# SiLabsProg2_V14C.net
KiCad netlist of a schematic drawn in Altium Designer
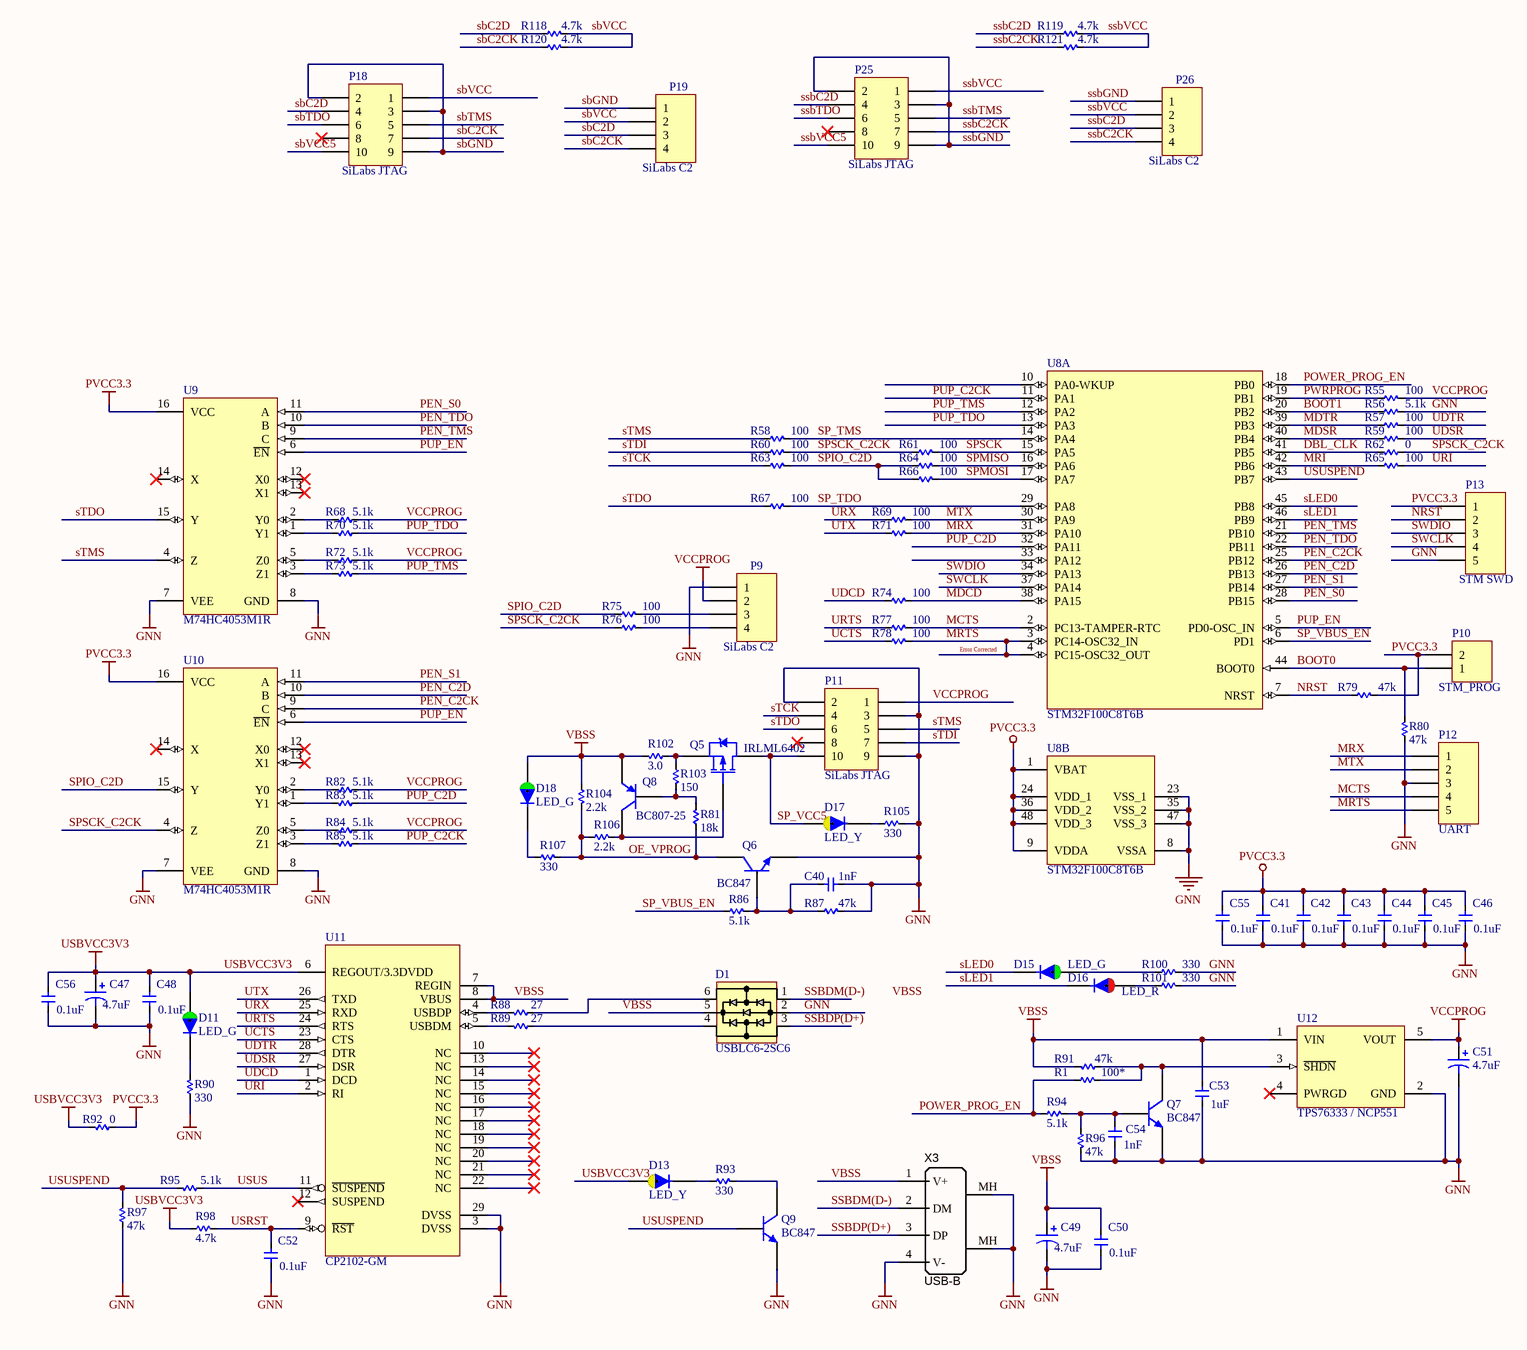
[diagram p0: SiLabsProg2_V14C.SchDoc]

(export (version "E")
  (design (tool "Eeschema 10.0.6"))
  (components
    (comp (ref "C40")
      (value "1nF")
      (footprint "R1608_CAP")
      (description "Capacitor")
      (fields (field (name "MANUFACTURER") "Generic Components") (field (name "PUBLISHER") "Altium Limited"))
      (libsource (lib "Passive_RC") (part "CAP"))
    )
    (comp (ref "C41")
      (value "0.1uF")
      (footprint "R1005_CAP")
      (description "Capacitor")
      (fields (field (name "MANUFACTURER") "Generic Components") (field (name "PUBLISHER") "Altium Limited"))
      (libsource (lib "Passive_RC") (part "CAP"))
    )
    (comp (ref "C42")
      (value "0.1uF")
      (footprint "R1005_CAP")
      (description "Capacitor")
      (fields (field (name "MANUFACTURER") "Generic Components") (field (name "PUBLISHER") "Altium Limited"))
      (libsource (lib "Passive_RC") (part "CAP"))
    )
    (comp (ref "C43")
      (value "0.1uF")
      (footprint "R1005_CAP")
      (description "Capacitor")
      (fields (field (name "MANUFACTURER") "Generic Components") (field (name "PUBLISHER") "Altium Limited"))
      (libsource (lib "Passive_RC") (part "CAP"))
    )
    (comp (ref "C44")
      (value "0.1uF")
      (footprint "R1005_CAP")
      (description "Capacitor")
      (fields (field (name "MANUFACTURER") "Generic Components") (field (name "PUBLISHER") "Altium Limited"))
      (libsource (lib "Passive_RC") (part "CAP"))
    )
    (comp (ref "C45")
      (value "0.1uF")
      (footprint "R1005_CAP")
      (description "Capacitor")
      (fields (field (name "MANUFACTURER") "Generic Components") (field (name "PUBLISHER") "Altium Limited"))
      (libsource (lib "Passive_RC") (part "CAP"))
    )
    (comp (ref "C46")
      (value "0.1uF")
      (footprint "R1005_CAP")
      (description "Capacitor")
      (fields (field (name "MANUFACTURER") "Generic Components") (field (name "PUBLISHER") "Altium Limited"))
      (libsource (lib "Passive_RC") (part "CAP"))
    )
    (comp (ref "C47")
      (value "4.7uF")
      (footprint "CAPC3225L")
      (description "Polarized Capacitor (Radial)")
      (fields (field (name "PUBLISHER") "Altium Limited"))
      (libsource (lib "Miscellaneous Devices") (part "Cap Pol1"))
    )
    (comp (ref "C48")
      (value "0.1uF")
      (footprint "R1005_CAP")
      (description "Capacitor")
      (fields (field (name "MANUFACTURER") "Generic Components") (field (name "PUBLISHER") "Altium Limited"))
      (libsource (lib "Passive_RC") (part "CAP"))
    )
    (comp (ref "C49")
      (value "4.7uF")
      (footprint "CAPC3225L")
      (description "Polarized Capacitor (Radial)")
      (fields (field (name "PUBLISHER") "Altium Limited"))
      (libsource (lib "Miscellaneous Devices") (part "Cap Pol1"))
    )
    (comp (ref "C50")
      (value "0.1uF")
      (footprint "R1005_CAP")
      (description "Capacitor")
      (fields (field (name "MANUFACTURER") "Generic Components") (field (name "PUBLISHER") "Altium Limited"))
      (libsource (lib "Passive_RC") (part "CAP"))
    )
    (comp (ref "C51")
      (value "4.7uF")
      (footprint "CAPC3225L")
      (description "Polarized Capacitor (Radial)")
      (fields (field (name "PUBLISHER") "Altium Limited"))
      (libsource (lib "Miscellaneous Devices") (part "Cap Pol1"))
    )
    (comp (ref "C52")
      (value "0.1uF")
      (footprint "R1005_CAP")
      (description "Capacitor")
      (fields (field (name "MANUFACTURER") "Generic Components") (field (name "PUBLISHER") "Altium Limited"))
      (libsource (lib "Passive_RC") (part "CAP"))
    )
    (comp (ref "C53")
      (value "1uF")
      (footprint "R1608_CAP")
      (description "Capacitor")
      (fields (field (name "MANUFACTURER") "Generic Components") (field (name "PUBLISHER") "Altium Limited"))
      (libsource (lib "Passive_RC") (part "CAP"))
    )
    (comp (ref "C54")
      (value "1nF")
      (footprint "R1608_CAP")
      (description "Capacitor")
      (fields (field (name "MANUFACTURER") "Generic Components") (field (name "PUBLISHER") "Altium Limited"))
      (libsource (lib "Passive_RC") (part "CAP"))
    )
    (comp (ref "C55")
      (value "0.1uF")
      (footprint "R1005_CAP")
      (description "Capacitor")
      (fields (field (name "MANUFACTURER") "Generic Components") (field (name "PUBLISHER") "Altium Limited"))
      (libsource (lib "Passive_RC") (part "CAP"))
    )
    (comp (ref "C56")
      (value "0.1uF")
      (footprint "R1005_CAP")
      (description "Capacitor")
      (fields (field (name "MANUFACTURER") "Generic Components") (field (name "PUBLISHER") "Altium Limited"))
      (libsource (lib "Passive_RC") (part "CAP"))
    )
    (comp (ref "D1")
      (value "USBLC6-2SC6")
      (footprint "SOT23-6")
      (libsource (lib "IntLib") (part "USBLC6-2P6"))
    )
    (comp (ref "D11")
      (value "LED_G")
      (footprint "LED3G")
      (fields (field (name "PUBLISHER") "Altium Limited"))
      (libsource (lib "IntLib") (part "LED_G"))
    )
    (comp (ref "D13")
      (value "LED_Y")
      (footprint "LED3Y")
      (fields (field (name "PUBLISHER") "Altium Limited"))
      (libsource (lib "IntLib") (part "LED_Y"))
    )
    (comp (ref "D15")
      (value "LED_G")
      (footprint "LED3G")
      (fields (field (name "PUBLISHER") "Altium Limited"))
      (libsource (lib "IntLib") (part "LED_G"))
    )
    (comp (ref "D16")
      (value "LED_R")
      (footprint "LED3R")
      (fields (field (name "PUBLISHER") "Altium Limited"))
      (libsource (lib "IntLib") (part "LED_R"))
    )
    (comp (ref "D17")
      (value "LED_Y")
      (footprint "LED3Y")
      (fields (field (name "PUBLISHER") "Altium Limited"))
      (libsource (lib "IntLib") (part "LED_Y"))
    )
    (comp (ref "D18")
      (value "LED_G")
      (footprint "LED3G")
      (fields (field (name "PUBLISHER") "Altium Limited"))
      (libsource (lib "IntLib") (part "LED_G"))
    )
    (comp (ref "P9")
      (value "SiLabs C2")
      (footprint "HDR1X4")
      (description "Header, 4-Pin")
      (fields (field (name "PUBLISHER") "Altium Limited"))
      (libsource (lib "Miscellaneous Connectors") (part "Header 4"))
    )
    (comp (ref "P10")
      (value "STM_PROG")
      (footprint "HDR1X2")
      (description "Header, 2-Pin")
      (fields (field (name "PUBLISHER") "Altium Limited"))
      (libsource (lib "Miscellaneous Connectors") (part "Header 2"))
    )
    (comp (ref "P11")
      (value "SiLabs JTAG")
      (footprint "HDR2X5")
      (description "Header, 5-Pin, Dual row")
      (fields (field (name "PUBLISHER") "Altium Limited"))
      (libsource (lib "Miscellaneous Connectors") (part "Header 5X2"))
    )
    (comp (ref "P12")
      (value "UART")
      (footprint "HDR1X5")
      (description "Header, 5-Pin")
      (fields (field (name "PUBLISHER") "Altium Limited"))
      (libsource (lib "Miscellaneous Connectors") (part "Header 5"))
    )
    (comp (ref "P13")
      (value "STM SWD")
      (footprint "HDR1X5")
      (description "Header, 5-Pin")
      (fields (field (name "PUBLISHER") "Altium Limited"))
      (libsource (lib "Miscellaneous Connectors") (part "Header 5"))
    )
    (comp (ref "P18")
      (value "SiLabs JTAG")
      (footprint "HDR2X5")
      (description "Header, 5-Pin, Dual row")
      (fields (field (name "PUBLISHER") "Altium Limited"))
      (libsource (lib "Miscellaneous Connectors") (part "Header 5X2"))
    )
    (comp (ref "P19")
      (value "SiLabs C2")
      (footprint "HDR1X4")
      (description "Header, 4-Pin")
      (fields (field (name "PUBLISHER") "Altium Limited"))
      (libsource (lib "Miscellaneous Connectors") (part "Header 4"))
    )
    (comp (ref "P25")
      (value "SiLabs JTAG")
      (footprint "HDR2X5")
      (description "Header, 5-Pin, Dual row")
      (fields (field (name "PUBLISHER") "Altium Limited"))
      (libsource (lib "Miscellaneous Connectors") (part "Header 5X2"))
    )
    (comp (ref "P26")
      (value "SiLabs C2")
      (footprint "HDR1X4")
      (description "Header, 4-Pin")
      (fields (field (name "PUBLISHER") "Altium Limited"))
      (libsource (lib "Miscellaneous Connectors") (part "Header 4"))
    )
    (comp (ref "Q5")
      (value "IRLML6402")
      (footprint "SOT23-1")
      (description "HEXFET Power MOSFET")
      (fields (field (name "PUBLISHER") "Altium Limited"))
      (libsource (lib "IR Discrete MOSFET - Power") (part "IRLML6401"))
    )
    (comp (ref "Q6")
      (value "BC847")
      (footprint "SOT23-1")
      (description "NPN General-purpose Transistor")
      (fields (field (name "PUBLISHER") "Altium Limited"))
      (libsource (lib "Philips Discrete BJT - Low Power") (part "BC847"))
    )
    (comp (ref "Q7")
      (value "BC847")
      (footprint "SOT23-1")
      (description "NPN General-purpose Transistor")
      (fields (field (name "PUBLISHER") "Altium Limited"))
      (libsource (lib "Philips Discrete BJT - Low Power") (part "BC847"))
    )
    (comp (ref "Q8")
      (value "BC807-25")
      (footprint "SOT23-1")
      (description "PNP General-purpose Transistor")
      (fields (field (name "PUBLISHER") "Altium Limited"))
      (libsource (lib "Philips Discrete BJT - Low Power") (part "BC807-25"))
    )
    (comp (ref "Q9")
      (value "BC847")
      (footprint "SOT23-1")
      (description "NPN General-purpose Transistor")
      (fields (field (name "PUBLISHER") "Altium Limited"))
      (libsource (lib "Philips Discrete BJT - Low Power") (part "BC847"))
    )
    (comp (ref "R1")
      (value "100*")
      (footprint "R1608_RES")
      (description "Resistor")
      (fields (field (name "MANUFACTURER") "Generic Components") (field (name "PUBLISHER") "Altium Limited"))
      (libsource (lib "Passive_RC") (part "RES"))
    )
    (comp (ref "R55")
      (value "100")
      (footprint "R1608_RES")
      (description "Resistor")
      (fields (field (name "MANUFACTURER") "Generic Components") (field (name "PUBLISHER") "Altium Limited"))
      (libsource (lib "Passive_RC") (part "RES"))
    )
    (comp (ref "R56")
      (value "5.1k")
      (footprint "R1608_RES")
      (description "Resistor")
      (fields (field (name "MANUFACTURER") "Generic Components") (field (name "PUBLISHER") "Altium Limited"))
      (libsource (lib "Passive_RC") (part "RES"))
    )
    (comp (ref "R57")
      (value "100")
      (footprint "R1608_RES")
      (description "Resistor")
      (fields (field (name "MANUFACTURER") "Generic Components") (field (name "PUBLISHER") "Altium Limited"))
      (libsource (lib "Passive_RC") (part "RES"))
    )
    (comp (ref "R58")
      (value "100")
      (footprint "R1608_RES")
      (description "Resistor")
      (fields (field (name "MANUFACTURER") "Generic Components") (field (name "PUBLISHER") "Altium Limited"))
      (libsource (lib "Passive_RC") (part "RES"))
    )
    (comp (ref "R59")
      (value "100")
      (footprint "R1608_RES")
      (description "Resistor")
      (fields (field (name "MANUFACTURER") "Generic Components") (field (name "PUBLISHER") "Altium Limited"))
      (libsource (lib "Passive_RC") (part "RES"))
    )
    (comp (ref "R60")
      (value "100")
      (footprint "R1608_RES")
      (description "Resistor")
      (fields (field (name "MANUFACTURER") "Generic Components") (field (name "PUBLISHER") "Altium Limited"))
      (libsource (lib "Passive_RC") (part "RES"))
    )
    (comp (ref "R61")
      (value "100")
      (footprint "R1608_RES")
      (description "Resistor")
      (fields (field (name "MANUFACTURER") "Generic Components") (field (name "PUBLISHER") "Altium Limited"))
      (libsource (lib "Passive_RC") (part "RES"))
    )
    (comp (ref "R62")
      (value "0")
      (footprint "R1608_RES")
      (description "Resistor")
      (fields (field (name "MANUFACTURER") "Generic Components") (field (name "PUBLISHER") "Altium Limited"))
      (libsource (lib "Passive_RC") (part "RES"))
    )
    (comp (ref "R63")
      (value "100")
      (footprint "R1608_RES")
      (description "Resistor")
      (fields (field (name "MANUFACTURER") "Generic Components") (field (name "PUBLISHER") "Altium Limited"))
      (libsource (lib "Passive_RC") (part "RES"))
    )
    (comp (ref "R64")
      (value "100")
      (footprint "R1608_RES")
      (description "Resistor")
      (fields (field (name "MANUFACTURER") "Generic Components") (field (name "PUBLISHER") "Altium Limited"))
      (libsource (lib "Passive_RC") (part "RES"))
    )
    (comp (ref "R65")
      (value "100")
      (footprint "R1608_RES")
      (description "Resistor")
      (fields (field (name "MANUFACTURER") "Generic Components") (field (name "PUBLISHER") "Altium Limited"))
      (libsource (lib "Passive_RC") (part "RES"))
    )
    (comp (ref "R66")
      (value "100")
      (footprint "R1608_RES")
      (description "Resistor")
      (fields (field (name "MANUFACTURER") "Generic Components") (field (name "PUBLISHER") "Altium Limited"))
      (libsource (lib "Passive_RC") (part "RES"))
    )
    (comp (ref "R67")
      (value "100")
      (footprint "R1608_RES")
      (description "Resistor")
      (fields (field (name "MANUFACTURER") "Generic Components") (field (name "PUBLISHER") "Altium Limited"))
      (libsource (lib "Passive_RC") (part "RES"))
    )
    (comp (ref "R68")
      (value "5.1k")
      (footprint "R1608_RES")
      (description "Resistor")
      (fields (field (name "MANUFACTURER") "Generic Components") (field (name "PUBLISHER") "Altium Limited"))
      (libsource (lib "Passive_RC") (part "RES"))
    )
    (comp (ref "R69")
      (value "100")
      (footprint "R1608_RES")
      (description "Resistor")
      (fields (field (name "MANUFACTURER") "Generic Components") (field (name "PUBLISHER") "Altium Limited"))
      (libsource (lib "Passive_RC") (part "RES"))
    )
    (comp (ref "R70")
      (value "5.1k")
      (footprint "R1608_RES")
      (description "Resistor")
      (fields (field (name "MANUFACTURER") "Generic Components") (field (name "PUBLISHER") "Altium Limited"))
      (libsource (lib "Passive_RC") (part "RES"))
    )
    (comp (ref "R71")
      (value "100")
      (footprint "R1608_RES")
      (description "Resistor")
      (fields (field (name "MANUFACTURER") "Generic Components") (field (name "PUBLISHER") "Altium Limited"))
      (libsource (lib "Passive_RC") (part "RES"))
    )
    (comp (ref "R72")
      (value "5.1k")
      (footprint "R1608_RES")
      (description "Resistor")
      (fields (field (name "MANUFACTURER") "Generic Components") (field (name "PUBLISHER") "Altium Limited"))
      (libsource (lib "Passive_RC") (part "RES"))
    )
    (comp (ref "R73")
      (value "5.1k")
      (footprint "R1608_RES")
      (description "Resistor")
      (fields (field (name "MANUFACTURER") "Generic Components") (field (name "PUBLISHER") "Altium Limited"))
      (libsource (lib "Passive_RC") (part "RES"))
    )
    (comp (ref "R74")
      (value "100")
      (footprint "R1608_RES")
      (description "Resistor")
      (fields (field (name "MANUFACTURER") "Generic Components") (field (name "PUBLISHER") "Altium Limited"))
      (libsource (lib "Passive_RC") (part "RES"))
    )
    (comp (ref "R75")
      (value "100")
      (footprint "R1608_RES")
      (description "Resistor")
      (fields (field (name "MANUFACTURER") "Generic Components") (field (name "PUBLISHER") "Altium Limited"))
      (libsource (lib "Passive_RC") (part "RES"))
    )
    (comp (ref "R76")
      (value "100")
      (footprint "R1608_RES")
      (description "Resistor")
      (fields (field (name "MANUFACTURER") "Generic Components") (field (name "PUBLISHER") "Altium Limited"))
      (libsource (lib "Passive_RC") (part "RES"))
    )
    (comp (ref "R77")
      (value "100")
      (footprint "R1608_RES")
      (description "Resistor")
      (fields (field (name "MANUFACTURER") "Generic Components") (field (name "PUBLISHER") "Altium Limited"))
      (libsource (lib "Passive_RC") (part "RES"))
    )
    (comp (ref "R78")
      (value "100")
      (footprint "R1608_RES")
      (description "Resistor")
      (fields (field (name "MANUFACTURER") "Generic Components") (field (name "PUBLISHER") "Altium Limited"))
      (libsource (lib "Passive_RC") (part "RES"))
    )
    (comp (ref "R79")
      (value "47k")
      (footprint "R1608_RES")
      (description "Resistor")
      (fields (field (name "MANUFACTURER") "Generic Components") (field (name "PUBLISHER") "Altium Limited"))
      (libsource (lib "Passive_RC") (part "RES"))
    )
    (comp (ref "R80")
      (value "47k")
      (footprint "R1608_RES")
      (description "Resistor")
      (fields (field (name "MANUFACTURER") "Generic Components") (field (name "PUBLISHER") "Altium Limited"))
      (libsource (lib "Passive_RC") (part "RES"))
    )
    (comp (ref "R81")
      (value "18k")
      (footprint "R1608_RES")
      (description "Resistor")
      (fields (field (name "MANUFACTURER") "Generic Components") (field (name "PUBLISHER") "Altium Limited"))
      (libsource (lib "Passive_RC") (part "RES"))
    )
    (comp (ref "R82")
      (value "5.1k")
      (footprint "R1608_RES")
      (description "Resistor")
      (fields (field (name "MANUFACTURER") "Generic Components") (field (name "PUBLISHER") "Altium Limited"))
      (libsource (lib "Passive_RC") (part "RES"))
    )
    (comp (ref "R83")
      (value "5.1k")
      (footprint "R1608_RES")
      (description "Resistor")
      (fields (field (name "MANUFACTURER") "Generic Components") (field (name "PUBLISHER") "Altium Limited"))
      (libsource (lib "Passive_RC") (part "RES"))
    )
    (comp (ref "R84")
      (value "5.1k")
      (footprint "R1608_RES")
      (description "Resistor")
      (fields (field (name "MANUFACTURER") "Generic Components") (field (name "PUBLISHER") "Altium Limited"))
      (libsource (lib "Passive_RC") (part "RES"))
    )
    (comp (ref "R85")
      (value "5.1k")
      (footprint "R1608_RES")
      (description "Resistor")
      (fields (field (name "MANUFACTURER") "Generic Components") (field (name "PUBLISHER") "Altium Limited"))
      (libsource (lib "Passive_RC") (part "RES"))
    )
    (comp (ref "R86")
      (value "5.1k")
      (footprint "R1608_RES")
      (description "Resistor")
      (fields (field (name "MANUFACTURER") "Generic Components") (field (name "PUBLISHER") "Altium Limited"))
      (libsource (lib "Passive_RC") (part "RES"))
    )
    (comp (ref "R87")
      (value "47k")
      (footprint "R1608_RES")
      (description "Resistor")
      (fields (field (name "MANUFACTURER") "Generic Components") (field (name "PUBLISHER") "Altium Limited"))
      (libsource (lib "Passive_RC") (part "RES"))
    )
    (comp (ref "R88")
      (value "27")
      (footprint "R1608_RES")
      (description "Resistor")
      (fields (field (name "MANUFACTURER") "Generic Components") (field (name "PUBLISHER") "Altium Limited"))
      (libsource (lib "Passive_RC") (part "RES"))
    )
    (comp (ref "R89")
      (value "27")
      (footprint "R1608_RES")
      (description "Resistor")
      (fields (field (name "MANUFACTURER") "Generic Components") (field (name "PUBLISHER") "Altium Limited"))
      (libsource (lib "Passive_RC") (part "RES"))
    )
    (comp (ref "R90")
      (value "330")
      (footprint "R1608_RES")
      (description "Resistor")
      (fields (field (name "MANUFACTURER") "Generic Components") (field (name "PUBLISHER") "Altium Limited"))
      (libsource (lib "Passive_RC") (part "RES"))
    )
    (comp (ref "R91")
      (value "47k")
      (footprint "R1608_RES")
      (description "Resistor")
      (fields (field (name "MANUFACTURER") "Generic Components") (field (name "PUBLISHER") "Altium Limited"))
      (libsource (lib "Passive_RC") (part "RES"))
    )
    (comp (ref "R92")
      (value "0")
      (footprint "R1608_RES")
      (description "Resistor")
      (fields (field (name "MANUFACTURER") "Generic Components") (field (name "PUBLISHER") "Altium Limited"))
      (libsource (lib "Passive_RC") (part "RES"))
    )
    (comp (ref "R93")
      (value "330")
      (footprint "R1608_RES")
      (description "Resistor")
      (fields (field (name "MANUFACTURER") "Generic Components") (field (name "PUBLISHER") "Altium Limited"))
      (libsource (lib "Passive_RC") (part "RES"))
    )
    (comp (ref "R94")
      (value "5.1k")
      (footprint "R1608_RES")
      (description "Resistor")
      (fields (field (name "MANUFACTURER") "Generic Components") (field (name "PUBLISHER") "Altium Limited"))
      (libsource (lib "Passive_RC") (part "RES"))
    )
    (comp (ref "R95")
      (value "5.1k")
      (footprint "R1608_RES")
      (description "Resistor")
      (fields (field (name "MANUFACTURER") "Generic Components") (field (name "PUBLISHER") "Altium Limited"))
      (libsource (lib "Passive_RC") (part "RES"))
    )
    (comp (ref "R96")
      (value "47k")
      (footprint "R1608_RES")
      (description "Resistor")
      (fields (field (name "MANUFACTURER") "Generic Components") (field (name "PUBLISHER") "Altium Limited"))
      (libsource (lib "Passive_RC") (part "RES"))
    )
    (comp (ref "R97")
      (value "47k")
      (footprint "R1608_RES")
      (description "Resistor")
      (fields (field (name "MANUFACTURER") "Generic Components") (field (name "PUBLISHER") "Altium Limited"))
      (libsource (lib "Passive_RC") (part "RES"))
    )
    (comp (ref "R98")
      (value "4.7k")
      (footprint "R1608_RES")
      (description "Resistor")
      (fields (field (name "MANUFACTURER") "Generic Components") (field (name "PUBLISHER") "Altium Limited"))
      (libsource (lib "Passive_RC") (part "RES"))
    )
    (comp (ref "R100")
      (value "330")
      (footprint "R1608_RES")
      (description "Resistor")
      (fields (field (name "MANUFACTURER") "Generic Components") (field (name "PUBLISHER") "Altium Limited"))
      (libsource (lib "Passive_RC") (part "RES"))
    )
    (comp (ref "R101")
      (value "330")
      (footprint "R1608_RES")
      (description "Resistor")
      (fields (field (name "MANUFACTURER") "Generic Components") (field (name "PUBLISHER") "Altium Limited"))
      (libsource (lib "Passive_RC") (part "RES"))
    )
    (comp (ref "R102")
      (value "3.0")
      (footprint "R1608_RES")
      (description "Resistor")
      (fields (field (name "MANUFACTURER") "Generic Components") (field (name "PUBLISHER") "Altium Limited"))
      (libsource (lib "Passive_RC") (part "RES"))
    )
    (comp (ref "R103")
      (value "150")
      (footprint "R1608_RES")
      (description "Resistor")
      (fields (field (name "MANUFACTURER") "Generic Components") (field (name "PUBLISHER") "Altium Limited"))
      (libsource (lib "Passive_RC") (part "RES"))
    )
    (comp (ref "R104")
      (value "2.2k")
      (footprint "R1608_RES")
      (description "Resistor")
      (fields (field (name "MANUFACTURER") "Generic Components") (field (name "PUBLISHER") "Altium Limited"))
      (libsource (lib "Passive_RC") (part "RES"))
    )
    (comp (ref "R105")
      (value "330")
      (footprint "R1608_RES")
      (description "Resistor")
      (fields (field (name "MANUFACTURER") "Generic Components") (field (name "PUBLISHER") "Altium Limited"))
      (libsource (lib "Passive_RC") (part "RES"))
    )
    (comp (ref "R106")
      (value "2.2k")
      (footprint "R1608_RES")
      (description "Resistor")
      (fields (field (name "MANUFACTURER") "Generic Components") (field (name "PUBLISHER") "Altium Limited"))
      (libsource (lib "Passive_RC") (part "RES"))
    )
    (comp (ref "R107")
      (value "330")
      (footprint "R1608_RES")
      (description "Resistor")
      (fields (field (name "MANUFACTURER") "Generic Components") (field (name "PUBLISHER") "Altium Limited"))
      (libsource (lib "Passive_RC") (part "RES"))
    )
    (comp (ref "R118")
      (value "4.7k")
      (footprint "R1608_RES")
      (description "Resistor")
      (fields
        (field (name "MANUFACTURER") "Generic Components")
        (field (name "Comment") "R")
        (field (name "PUBLISHER") "Altium Limited")
      )
      (libsource (lib "Passive_RC") (part "R"))
    )
    (comp (ref "R119")
      (value "4.7k")
      (footprint "R1608_RES")
      (description "Resistor")
      (fields
        (field (name "MANUFACTURER") "Generic Components")
        (field (name "Comment") "R")
        (field (name "PUBLISHER") "Altium Limited")
      )
      (libsource (lib "Passive_RC") (part "R"))
    )
    (comp (ref "R120")
      (value "4.7k")
      (footprint "R1608_RES")
      (description "Resistor")
      (fields
        (field (name "MANUFACTURER") "Generic Components")
        (field (name "Comment") "R")
        (field (name "PUBLISHER") "Altium Limited")
      )
      (libsource (lib "Passive_RC") (part "R"))
    )
    (comp (ref "R121")
      (value "4.7k")
      (footprint "R1608_RES")
      (description "Resistor")
      (fields
        (field (name "MANUFACTURER") "Generic Components")
        (field (name "Comment") "R")
        (field (name "PUBLISHER") "Altium Limited")
      )
      (libsource (lib "Passive_RC") (part "R"))
    )
    (comp (ref "U8")
      (value "STM32F100C8T6B")
      (footprint "LQFP48_N")
      (libsource (lib "STMicroelectronics STM32 F1") (part "STM32F100C8T6B"))
    )
    (comp (ref "U9")
      (value "M74HC4053M1R")
      (footprint "SO16_N")
      (description "Analog Multiplexer/Demultiplexer Triple 2-Channel")
      (fields (field (name "PUBLISHER") "Altium Limited"))
      (libsource (lib "ST Logic Multiplexer") (part "M74HC4053M1R"))
    )
    (comp (ref "U10")
      (value "M74HC4053M1R")
      (footprint "SO16_N")
      (description "Analog Multiplexer/Demultiplexer Triple 2-Channel")
      (fields (field (name "PUBLISHER") "Altium Limited"))
      (libsource (lib "ST Logic Multiplexer") (part "M74HC4053M1R"))
    )
    (comp (ref "U11")
      (value "CP2102-GM")
      (footprint "QFN28")
      (description "Single Chip USB to UART Bridge, USB 2.0, 1024Bytes EEPROM.")
      (fields
        (field (name "DIGIKEYPARTNUMBER") "336-1160-ND")
        (field (name "PUBLISHER") "A and A System Co., Ltd.")
      )
      (libsource (lib "IntLib") (part "CP2102-GM"))
    )
    (comp (ref "U12")
      (value "TPS76333 / NCP551")
      (footprint "SOT23-5D")
      (fields (field (name "PUBLISHER") "Altium Limited"))
      (libsource (lib "IntLib") (part "TPS76333"))
    )
    (comp (ref "X3")
      (value "USB-B")
      (footprint "USB_TypeB_Tyco")
      (description "Connector THT Type B USB connector")
      (libsource (lib "PBL - Connectors") (part "USB_TypeB"))
    )
  )
  (nets
    (net (code "1") (name "/BOOT0") (class "Default")
      (node (ref "P10") (pin "1") (pinfunction "1_1") (pintype "passive"))
      (node (ref "R80") (pin "2") (pinfunction "2_2") (pintype "passive"))
      (node (ref "U8") (pin "44") (pinfunction "BOOT0_44") (pintype "input"))
    )
    (net (code "2") (name "/BOOT1") (class "Default")
      (node (ref "R56") (pin "1") (pinfunction "1_1") (pintype "passive"))
      (node (ref "U8") (pin "20") (pinfunction "PB2_20") (pintype "bidirectional"))
    )
    (net (code "3") (name "/DBL_CLK") (class "Default")
      (node (ref "R62") (pin "2") (pinfunction "2_2") (pintype "passive"))
      (node (ref "U8") (pin "41") (pinfunction "PB5_41") (pintype "bidirectional"))
    )
    (net (code "4") (name "/MCTS") (class "Default")
      (node (ref "P12") (pin "4") (pinfunction "4_4") (pintype "passive"))
      (node (ref "R77") (pin "2") (pinfunction "2_2") (pintype "passive"))
      (node (ref "U8") (pin "2") (pinfunction "PC13-TAMPER-RTC_2") (pintype "bidirectional"))
    )
    (net (code "5") (name "/MDCD") (class "Default")
      (node (ref "R74") (pin "2") (pinfunction "2_2") (pintype "passive"))
      (node (ref "U8") (pin "38") (pinfunction "PA15_38") (pintype "bidirectional"))
    )
    (net (code "6") (name "/MDSR") (class "Default")
      (node (ref "R59") (pin "1") (pinfunction "1_1") (pintype "passive"))
      (node (ref "U8") (pin "40") (pinfunction "PB4_40") (pintype "bidirectional"))
    )
    (net (code "7") (name "/MDTR") (class "Default")
      (node (ref "R57") (pin "1") (pinfunction "1_1") (pintype "passive"))
      (node (ref "U8") (pin "39") (pinfunction "PB3_39") (pintype "bidirectional"))
    )
    (net (code "8") (name "/MRI") (class "Default")
      (node (ref "R65") (pin "1") (pinfunction "1_1") (pintype "passive"))
      (node (ref "U8") (pin "42") (pinfunction "PB6_42") (pintype "bidirectional"))
    )
    (net (code "9") (name "/MRTS") (class "Default")
      (node (ref "P12") (pin "5") (pinfunction "5_5") (pintype "passive"))
      (node (ref "R78") (pin "2") (pinfunction "2_2") (pintype "passive"))
      (node (ref "U8") (pin "3") (pinfunction "PC14-OSC32_IN_3") (pintype "bidirectional"))
      (node (ref "U8") (pin "4") (pinfunction "PC15-OSC32_OUT_4") (pintype "bidirectional"))
    )
    (net (code "10") (name "/MRX") (class "Default")
      (node (ref "P12") (pin "1") (pinfunction "1_1") (pintype "passive"))
      (node (ref "R71") (pin "2") (pinfunction "2_2") (pintype "passive"))
      (node (ref "U8") (pin "31") (pinfunction "PA10_31") (pintype "bidirectional"))
    )
    (net (code "11") (name "/MTX") (class "Default")
      (node (ref "P12") (pin "2") (pinfunction "2_2") (pintype "passive"))
      (node (ref "R69") (pin "2") (pinfunction "2_2") (pintype "passive"))
      (node (ref "U8") (pin "30") (pinfunction "PA9_30") (pintype "bidirectional"))
    )
    (net (code "12") (name "/NRST") (class "Default")
      (node (ref "P13") (pin "2") (pinfunction "2_2") (pintype "passive"))
      (node (ref "R79") (pin "1") (pinfunction "1_1") (pintype "passive"))
      (node (ref "U8") (pin "7") (pinfunction "NRST_7") (pintype "bidirectional"))
    )
    (net (code "13") (name "/OE_VPROG") (class "Default")
      (node (ref "Q6") (pin "3") (pinfunction "C_3") (pintype "passive"))
      (node (ref "R104") (pin "2") (pinfunction "2_2") (pintype "passive"))
      (node (ref "R106") (pin "1") (pinfunction "1_1") (pintype "passive"))
      (node (ref "R107") (pin "2") (pinfunction "2_2") (pintype "passive"))
      (node (ref "R81") (pin "1") (pinfunction "1_1") (pintype "passive"))
    )
    (net (code "14") (name "/PEN_C2CK") (class "Default")
      (node (ref "U10") (pin "9") (pinfunction "C_9") (pintype "input"))
      (node (ref "U8") (pin "25") (pinfunction "PB12_25") (pintype "bidirectional"))
    )
    (net (code "15") (name "/PEN_C2D") (class "Default")
      (node (ref "U10") (pin "10") (pinfunction "B_10") (pintype "input"))
      (node (ref "U8") (pin "26") (pinfunction "PB13_26") (pintype "bidirectional"))
    )
    (net (code "16") (name "/PEN_S0") (class "Default")
      (node (ref "U8") (pin "28") (pinfunction "PB15_28") (pintype "bidirectional"))
      (node (ref "U9") (pin "11") (pinfunction "A_11") (pintype "input"))
    )
    (net (code "17") (name "/PEN_S1") (class "Default")
      (node (ref "U10") (pin "11") (pinfunction "A_11") (pintype "input"))
      (node (ref "U8") (pin "27") (pinfunction "PB14_27") (pintype "bidirectional"))
    )
    (net (code "18") (name "/PEN_TDO") (class "Default")
      (node (ref "U8") (pin "22") (pinfunction "PB11_22") (pintype "bidirectional"))
      (node (ref "U9") (pin "10") (pinfunction "B_10") (pintype "input"))
    )
    (net (code "19") (name "/PEN_TMS") (class "Default")
      (node (ref "U8") (pin "21") (pinfunction "PB10_21") (pintype "bidirectional"))
      (node (ref "U9") (pin "9") (pinfunction "C_9") (pintype "input"))
    )
    (net (code "20") (name "/POWER_PROG_EN") (class "Default")
      (node (ref "R1") (pin "1") (pinfunction "1_1") (pintype "passive"))
      (node (ref "R94") (pin "1") (pinfunction "1_1") (pintype "passive"))
      (node (ref "U8") (pin "18") (pinfunction "PB0_18") (pintype "bidirectional"))
    )
    (net (code "21") (name "/PUP_C2CK") (class "Default")
      (node (ref "R85") (pin "1") (pinfunction "1_1") (pintype "passive"))
      (node (ref "U8") (pin "11") (pinfunction "PA1_11") (pintype "bidirectional"))
    )
    (net (code "22") (name "/PUP_C2D") (class "Default")
      (node (ref "R83") (pin "1") (pinfunction "1_1") (pintype "passive"))
      (node (ref "U8") (pin "32") (pinfunction "PA11_32") (pintype "bidirectional"))
    )
    (net (code "23") (name "/PUP_EN") (class "Default")
      (node (ref "U10") (pin "6") (pinfunction "~{EN}_6") (pintype "input"))
      (node (ref "U8") (pin "5") (pinfunction "PD0-OSC_IN_5") (pintype "bidirectional"))
      (node (ref "U9") (pin "6") (pinfunction "~{EN}_6") (pintype "input"))
    )
    (net (code "24") (name "/PUP_TDO") (class "Default")
      (node (ref "R70") (pin "1") (pinfunction "1_1") (pintype "passive"))
      (node (ref "U8") (pin "13") (pinfunction "PA3_13") (pintype "bidirectional"))
    )
    (net (code "25") (name "/PUP_TMS") (class "Default")
      (node (ref "R73") (pin "1") (pinfunction "1_1") (pintype "passive"))
      (node (ref "U8") (pin "12") (pinfunction "PA2_12") (pintype "bidirectional"))
    )
    (net (code "26") (name "/PWRPROG") (class "Default")
      (node (ref "R55") (pin "1") (pinfunction "1_1") (pintype "passive"))
      (node (ref "U8") (pin "19") (pinfunction "PB1_19") (pintype "bidirectional"))
    )
    (net (code "27") (name "/SPIO_C2D") (class "Default")
      (node (ref "R63") (pin "2") (pinfunction "2_2") (pintype "passive"))
      (node (ref "R64") (pin "1") (pinfunction "1_1") (pintype "passive"))
      (node (ref "R66") (pin "1") (pinfunction "1_1") (pintype "passive"))
      (node (ref "R75") (pin "1") (pinfunction "1_1") (pintype "passive"))
      (node (ref "U10") (pin "15") (pinfunction "Y_15") (pintype "bidirectional"))
    )
    (net (code "28") (name "/SPMISO") (class "Default")
      (node (ref "R64") (pin "2") (pinfunction "2_2") (pintype "passive"))
      (node (ref "U8") (pin "16") (pinfunction "PA6_16") (pintype "bidirectional"))
    )
    (net (code "29") (name "/SPMOSI") (class "Default")
      (node (ref "R66") (pin "2") (pinfunction "2_2") (pintype "passive"))
      (node (ref "U8") (pin "17") (pinfunction "PA7_17") (pintype "bidirectional"))
    )
    (net (code "30") (name "/SPSCK") (class "Default")
      (node (ref "R61") (pin "2") (pinfunction "2_2") (pintype "passive"))
      (node (ref "U8") (pin "15") (pinfunction "PA5_15") (pintype "bidirectional"))
    )
    (net (code "31") (name "/SPSCK_C2CK") (class "Default")
      (node (ref "R60") (pin "2") (pinfunction "2_2") (pintype "passive"))
      (node (ref "R61") (pin "1") (pinfunction "1_1") (pintype "passive"))
      (node (ref "R62") (pin "1") (pinfunction "1_1") (pintype "passive"))
      (node (ref "R76") (pin "1") (pinfunction "1_1") (pintype "passive"))
      (node (ref "U10") (pin "4") (pinfunction "Z_4") (pintype "bidirectional"))
    )
    (net (code "32") (name "/SP_TDO") (class "Default")
      (node (ref "R67") (pin "2") (pinfunction "2_2") (pintype "passive"))
      (node (ref "U8") (pin "29") (pinfunction "PA8_29") (pintype "bidirectional"))
    )
    (net (code "33") (name "/SP_TMS") (class "Default")
      (node (ref "R58") (pin "2") (pinfunction "2_2") (pintype "passive"))
      (node (ref "U8") (pin "14") (pinfunction "PA4_14") (pintype "bidirectional"))
    )
    (net (code "34") (name "/SP_VBUS_EN") (class "Default")
      (node (ref "R86") (pin "1") (pinfunction "1_1") (pintype "passive"))
      (node (ref "U8") (pin "6") (pinfunction "PD1_6") (pintype "bidirectional"))
    )
    (net (code "35") (name "/SP_VCC5") (class "Default")
      (node (ref "D17") (pin "2") (pinfunction "A_2") (pintype "passive"))
      (node (ref "P11") (pin "10") (pinfunction "10_10") (pintype "passive"))
      (node (ref "Q5") (pin "3") (pinfunction "D_3") (pintype "passive"))
    )
    (net (code "36") (name "/SSBDM(D-)") (class "Default")
      (node (ref "D1") (pin "1") (pinfunction "IO1_1") (pintype "passive"))
      (node (ref "X3") (pin "2") (pinfunction "DM_2") (pintype "passive"))
    )
    (net (code "37") (name "/SSBDP(D+)") (class "Default")
      (node (ref "D1") (pin "3") (pinfunction "IO3_3") (pintype "passive"))
      (node (ref "X3") (pin "3") (pinfunction "DP_3") (pintype "passive"))
    )
    (net (code "38") (name "/SWCLK") (class "Default")
      (node (ref "P13") (pin "4") (pinfunction "4_4") (pintype "passive"))
      (node (ref "U8") (pin "37") (pinfunction "PA14_37") (pintype "bidirectional"))
    )
    (net (code "39") (name "/SWDIO") (class "Default")
      (node (ref "P13") (pin "3") (pinfunction "3_3") (pintype "passive"))
      (node (ref "U8") (pin "34") (pinfunction "PA13_34") (pintype "bidirectional"))
    )
    (net (code "40") (name "/UCTS") (class "Default")
      (node (ref "R78") (pin "1") (pinfunction "1_1") (pintype "passive"))
      (node (ref "U11") (pin "23") (pinfunction "CTS_23") (pintype "input"))
    )
    (net (code "41") (name "/UDCD") (class "Default")
      (node (ref "R74") (pin "1") (pinfunction "1_1") (pintype "passive"))
      (node (ref "U11") (pin "1") (pinfunction "DCD_1") (pintype "input"))
    )
    (net (code "42") (name "/UDSR") (class "Default")
      (node (ref "R59") (pin "2") (pinfunction "2_2") (pintype "passive"))
      (node (ref "U11") (pin "27") (pinfunction "DSR_27") (pintype "input"))
    )
    (net (code "43") (name "/UDTR") (class "Default")
      (node (ref "R57") (pin "2") (pinfunction "2_2") (pintype "passive"))
      (node (ref "U11") (pin "28") (pinfunction "DTR_28") (pintype "output"))
    )
    (net (code "44") (name "/URI") (class "Default")
      (node (ref "R65") (pin "2") (pinfunction "2_2") (pintype "passive"))
      (node (ref "U11") (pin "2") (pinfunction "RI_2") (pintype "input"))
    )
    (net (code "45") (name "/URTS") (class "Default")
      (node (ref "R77") (pin "1") (pinfunction "1_1") (pintype "passive"))
      (node (ref "U11") (pin "24") (pinfunction "RTS_24") (pintype "output"))
    )
    (net (code "46") (name "/URX") (class "Default")
      (node (ref "R69") (pin "1") (pinfunction "1_1") (pintype "passive"))
      (node (ref "U11") (pin "25") (pinfunction "RXD_25") (pintype "input"))
    )
    (net (code "47") (name "/USRST") (class "Default")
      (node (ref "C52") (pin "2") (pinfunction "2_2") (pintype "passive"))
      (node (ref "R98") (pin "2") (pinfunction "2_2") (pintype "passive"))
      (node (ref "U11") (pin "9") (pinfunction "~{RST}_9") (pintype "bidirectional"))
    )
    (net (code "48") (name "/USUS") (class "Default")
      (node (ref "R95") (pin "1") (pinfunction "1_1") (pintype "passive"))
      (node (ref "U11") (pin "11") (pinfunction "~{SUSPEND}_11") (pintype "output"))
    )
    (net (code "49") (name "/USUSPEND") (class "Default")
      (node (ref "Q9") (pin "1") (pinfunction "B_1") (pintype "passive"))
      (node (ref "R95") (pin "2") (pinfunction "2_2") (pintype "passive"))
      (node (ref "R97") (pin "2") (pinfunction "2_2") (pintype "passive"))
      (node (ref "U8") (pin "43") (pinfunction "PB7_43") (pintype "bidirectional"))
    )
    (net (code "50") (name "/UTX") (class "Default")
      (node (ref "R71") (pin "1") (pinfunction "1_1") (pintype "passive"))
      (node (ref "U11") (pin "26") (pinfunction "TXD_26") (pintype "output"))
    )
    (net (code "51") (name "/sLED0") (class "Default")
      (node (ref "D15") (pin "1") (pinfunction "K_1") (pintype "passive"))
      (node (ref "U8") (pin "45") (pinfunction "PB8_45") (pintype "bidirectional"))
    )
    (net (code "52") (name "/sLED1") (class "Default")
      (node (ref "D16") (pin "1") (pinfunction "K_1") (pintype "passive"))
      (node (ref "U8") (pin "46") (pinfunction "PB9_46") (pintype "bidirectional"))
    )
    (net (code "53") (name "/sTCK") (class "Default")
      (node (ref "P11") (pin "4") (pinfunction "4_4") (pintype "passive"))
      (node (ref "R63") (pin "1") (pinfunction "1_1") (pintype "passive"))
    )
    (net (code "54") (name "/sTDI") (class "Default")
      (node (ref "P11") (pin "7") (pinfunction "7_7") (pintype "passive"))
      (node (ref "R60") (pin "1") (pinfunction "1_1") (pintype "passive"))
    )
    (net (code "55") (name "/sTDO") (class "Default")
      (node (ref "P11") (pin "6") (pinfunction "6_6") (pintype "passive"))
      (node (ref "R67") (pin "1") (pinfunction "1_1") (pintype "passive"))
      (node (ref "U9") (pin "15") (pinfunction "Y_15") (pintype "bidirectional"))
    )
    (net (code "56") (name "/sTMS") (class "Default")
      (node (ref "P11") (pin "5") (pinfunction "5_5") (pintype "passive"))
      (node (ref "R58") (pin "1") (pinfunction "1_1") (pintype "passive"))
      (node (ref "U9") (pin "4") (pinfunction "Z_4") (pintype "bidirectional"))
    )
    (net (code "57") (name "/sbC2CK") (class "Default")
      (node (ref "P18") (pin "7") (pinfunction "7_7") (pintype "passive"))
      (node (ref "P19") (pin "4") (pinfunction "4_4") (pintype "passive"))
      (node (ref "R120") (pin "1") (pinfunction "1_1") (pintype "passive"))
    )
    (net (code "58") (name "/sbC2D") (class "Default")
      (node (ref "P18") (pin "4") (pinfunction "4_4") (pintype "passive"))
      (node (ref "P19") (pin "3") (pinfunction "3_3") (pintype "passive"))
      (node (ref "R118") (pin "1") (pinfunction "1_1") (pintype "passive"))
    )
    (net (code "59") (name "/sbGND") (class "Default")
      (node (ref "P18") (pin "2") (pinfunction "2_2") (pintype "passive"))
      (node (ref "P18") (pin "3") (pinfunction "3_3") (pintype "passive"))
      (node (ref "P18") (pin "9") (pinfunction "9_9") (pintype "passive"))
      (node (ref "P19") (pin "1") (pinfunction "1_1") (pintype "passive"))
    )
    (net (code "60") (name "/sbTDO") (class "Default")
      (node (ref "P18") (pin "6") (pinfunction "6_6") (pintype "passive"))
    )
    (net (code "61") (name "/sbTMS") (class "Default")
      (node (ref "P18") (pin "5") (pinfunction "5_5") (pintype "passive"))
    )
    (net (code "62") (name "/sbVCC") (class "Default")
      (node (ref "P18") (pin "1") (pinfunction "1_1") (pintype "passive"))
      (node (ref "P19") (pin "2") (pinfunction "2_2") (pintype "passive"))
      (node (ref "R118") (pin "2") (pinfunction "2_2") (pintype "passive"))
      (node (ref "R120") (pin "2") (pinfunction "2_2") (pintype "passive"))
    )
    (net (code "63") (name "/sbVCC5") (class "Default")
      (node (ref "P18") (pin "10") (pinfunction "10_10") (pintype "passive"))
    )
    (net (code "64") (name "/ssbC2CK") (class "Default")
      (node (ref "P25") (pin "7") (pinfunction "7_7") (pintype "passive"))
      (node (ref "P26") (pin "4") (pinfunction "4_4") (pintype "passive"))
      (node (ref "R121") (pin "1") (pinfunction "1_1") (pintype "passive"))
    )
    (net (code "65") (name "/ssbC2D") (class "Default")
      (node (ref "P25") (pin "4") (pinfunction "4_4") (pintype "passive"))
      (node (ref "P26") (pin "3") (pinfunction "3_3") (pintype "passive"))
      (node (ref "R119") (pin "1") (pinfunction "1_1") (pintype "passive"))
    )
    (net (code "66") (name "/ssbGND") (class "Default")
      (node (ref "P25") (pin "2") (pinfunction "2_2") (pintype "passive"))
      (node (ref "P25") (pin "3") (pinfunction "3_3") (pintype "passive"))
      (node (ref "P25") (pin "9") (pinfunction "9_9") (pintype "passive"))
      (node (ref "P26") (pin "1") (pinfunction "1_1") (pintype "passive"))
    )
    (net (code "67") (name "/ssbTDO") (class "Default")
      (node (ref "P25") (pin "6") (pinfunction "6_6") (pintype "passive"))
    )
    (net (code "68") (name "/ssbTMS") (class "Default")
      (node (ref "P25") (pin "5") (pinfunction "5_5") (pintype "passive"))
    )
    (net (code "69") (name "/ssbVCC") (class "Default")
      (node (ref "P25") (pin "1") (pinfunction "1_1") (pintype "passive"))
      (node (ref "P26") (pin "2") (pinfunction "2_2") (pintype "passive"))
      (node (ref "R119") (pin "2") (pinfunction "2_2") (pintype "passive"))
      (node (ref "R121") (pin "2") (pinfunction "2_2") (pintype "passive"))
    )
    (net (code "70") (name "/ssbVCC5") (class "Default")
      (node (ref "P25") (pin "10") (pinfunction "10_10") (pintype "passive"))
    )
    (net (code "71") (name "GNN") (class "Default")
      (node (ref "C40") (pin "1") (pinfunction "1_1") (pintype "passive"))
      (node (ref "C41") (pin "1") (pinfunction "1_1") (pintype "passive"))
      (node (ref "C42") (pin "1") (pinfunction "1_1") (pintype "passive"))
      (node (ref "C43") (pin "1") (pinfunction "1_1") (pintype "passive"))
      (node (ref "C44") (pin "1") (pinfunction "1_1") (pintype "passive"))
      (node (ref "C45") (pin "1") (pinfunction "1_1") (pintype "passive"))
      (node (ref "C46") (pin "1") (pinfunction "1_1") (pintype "passive"))
      (node (ref "C47") (pin "2") (pinfunction "2_2") (pintype "passive"))
      (node (ref "C48") (pin "1") (pinfunction "1_1") (pintype "passive"))
      (node (ref "C49") (pin "2") (pinfunction "2_2") (pintype "passive"))
      (node (ref "C50") (pin "1") (pinfunction "1_1") (pintype "passive"))
      (node (ref "C51") (pin "2") (pinfunction "2_2") (pintype "passive"))
      (node (ref "C52") (pin "1") (pinfunction "1_1") (pintype "passive"))
      (node (ref "C53") (pin "1") (pinfunction "1_1") (pintype "passive"))
      (node (ref "C54") (pin "1") (pinfunction "1_1") (pintype "passive"))
      (node (ref "C55") (pin "1") (pinfunction "1_1") (pintype "passive"))
      (node (ref "C56") (pin "1") (pinfunction "1_1") (pintype "passive"))
      (node (ref "D1") (pin "2") (pinfunction "GND_2") (pintype "passive"))
      (node (ref "P11") (pin "2") (pinfunction "2_2") (pintype "passive"))
      (node (ref "P11") (pin "3") (pinfunction "3_3") (pintype "passive"))
      (node (ref "P11") (pin "9") (pinfunction "9_9") (pintype "passive"))
      (node (ref "P12") (pin "3") (pinfunction "3_3") (pintype "passive"))
      (node (ref "P13") (pin "5") (pinfunction "5_5") (pintype "passive"))
      (node (ref "P9") (pin "1") (pinfunction "1_1") (pintype "passive"))
      (node (ref "Q6") (pin "2") (pinfunction "E_2") (pintype "passive"))
      (node (ref "Q7") (pin "2") (pinfunction "E_2") (pintype "passive"))
      (node (ref "Q9") (pin "2") (pinfunction "E_2") (pintype "passive"))
      (node (ref "R100") (pin "2") (pinfunction "2_2") (pintype "passive"))
      (node (ref "R101") (pin "2") (pinfunction "2_2") (pintype "passive"))
      (node (ref "R105") (pin "2") (pinfunction "2_2") (pintype "passive"))
      (node (ref "R56") (pin "2") (pinfunction "2_2") (pintype "passive"))
      (node (ref "R80") (pin "1") (pinfunction "1_1") (pintype "passive"))
      (node (ref "R87") (pin "2") (pinfunction "2_2") (pintype "passive"))
      (node (ref "R90") (pin "1") (pinfunction "1_1") (pintype "passive"))
      (node (ref "R96") (pin "2") (pinfunction "2_2") (pintype "passive"))
      (node (ref "R97") (pin "1") (pinfunction "1_1") (pintype "passive"))
      (node (ref "U10") (pin "7") (pinfunction "VEE_7") (pintype "power_in"))
      (node (ref "U10") (pin "8") (pinfunction "GND_8") (pintype "power_in"))
      (node (ref "U11") (pin "29") (pinfunction "DVSS_29") (pintype "power_in"))
      (node (ref "U11") (pin "3") (pinfunction "DVSS_3") (pintype "power_in"))
      (node (ref "U12") (pin "2") (pinfunction "GND_2") (pintype "power_in"))
      (node (ref "U8") (pin "23") (pinfunction "VSS_1_23") (pintype "power_in"))
      (node (ref "U8") (pin "35") (pinfunction "VSS_2_35") (pintype "power_in"))
      (node (ref "U8") (pin "47") (pinfunction "VSS_3_47") (pintype "power_in"))
      (node (ref "U8") (pin "8") (pinfunction "VSSA_8") (pintype "power_in"))
      (node (ref "U9") (pin "7") (pinfunction "VEE_7") (pintype "power_in"))
      (node (ref "U9") (pin "8") (pinfunction "GND_8") (pintype "power_in"))
      (node (ref "X3") (pin "4") (pinfunction "V-_4") (pintype "passive"))
      (node (ref "X3") (pin "MH") (pinfunction "Shell_MH") (pintype "passive"))
    )
    (net (code "72") (name "Net-(D1-IO2)") (class "Default")
      (node (ref "D1") (pin "6") (pinfunction "IO2_6") (pintype "passive"))
      (node (ref "R88") (pin "1") (pinfunction "1_1") (pintype "passive"))
    )
    (net (code "73") (name "Net-(D1-IO4)") (class "Default")
      (node (ref "D1") (pin "4") (pinfunction "IO4_4") (pintype "passive"))
      (node (ref "R89") (pin "1") (pinfunction "1_1") (pintype "passive"))
    )
    (net (code "74") (name "Net-(D11-K)") (class "Default")
      (node (ref "D11") (pin "1") (pinfunction "K_1") (pintype "passive"))
      (node (ref "R90") (pin "2") (pinfunction "2_2") (pintype "passive"))
    )
    (net (code "75") (name "Net-(D13-K)") (class "Default")
      (node (ref "D13") (pin "1") (pinfunction "K_1") (pintype "passive"))
      (node (ref "R93") (pin "1") (pinfunction "1_1") (pintype "passive"))
    )
    (net (code "76") (name "Net-(D15-A)") (class "Default")
      (node (ref "D15") (pin "2") (pinfunction "A_2") (pintype "passive"))
      (node (ref "R100") (pin "1") (pinfunction "1_1") (pintype "passive"))
    )
    (net (code "77") (name "Net-(D16-A)") (class "Default")
      (node (ref "D16") (pin "2") (pinfunction "A_2") (pintype "passive"))
      (node (ref "R101") (pin "1") (pinfunction "1_1") (pintype "passive"))
    )
    (net (code "78") (name "Net-(D17-K)") (class "Default")
      (node (ref "D17") (pin "1") (pinfunction "K_1") (pintype "passive"))
      (node (ref "R105") (pin "1") (pinfunction "1_1") (pintype "passive"))
    )
    (net (code "79") (name "Net-(D18-K)") (class "Default")
      (node (ref "D18") (pin "1") (pinfunction "K_1") (pintype "passive"))
      (node (ref "R107") (pin "1") (pinfunction "1_1") (pintype "passive"))
    )
    (net (code "80") (name "Net-(P9-Pad3)") (class "Default")
      (node (ref "P9") (pin "3") (pinfunction "3_3") (pintype "passive"))
      (node (ref "R75") (pin "2") (pinfunction "2_2") (pintype "passive"))
    )
    (net (code "81") (name "Net-(P9-Pad4)") (class "Default")
      (node (ref "P9") (pin "4") (pinfunction "4_4") (pintype "passive"))
      (node (ref "R76") (pin "2") (pinfunction "2_2") (pintype "passive"))
    )
    (net (code "82") (name "Net-(Q5-G)") (class "Default")
      (node (ref "Q5") (pin "1") (pinfunction "G_1") (pintype "passive"))
      (node (ref "Q8") (pin "3") (pinfunction "C_3") (pintype "passive"))
      (node (ref "R106") (pin "2") (pinfunction "2_2") (pintype "passive"))
    )
    (net (code "83") (name "Net-(Q5-S)") (class "Default")
      (node (ref "Q5") (pin "2") (pinfunction "S_2") (pintype "passive"))
      (node (ref "R102") (pin "1") (pinfunction "1_1") (pintype "passive"))
      (node (ref "R103") (pin "1") (pinfunction "1_1") (pintype "passive"))
    )
    (net (code "84") (name "Net-(Q6-B)") (class "Default")
      (node (ref "C40") (pin "2") (pinfunction "2_2") (pintype "passive"))
      (node (ref "Q6") (pin "1") (pinfunction "B_1") (pintype "passive"))
      (node (ref "R86") (pin "2") (pinfunction "2_2") (pintype "passive"))
      (node (ref "R87") (pin "1") (pinfunction "1_1") (pintype "passive"))
    )
    (net (code "85") (name "Net-(Q7-B)") (class "Default")
      (node (ref "C54") (pin "2") (pinfunction "2_2") (pintype "passive"))
      (node (ref "Q7") (pin "1") (pinfunction "B_1") (pintype "passive"))
      (node (ref "R94") (pin "2") (pinfunction "2_2") (pintype "passive"))
      (node (ref "R96") (pin "1") (pinfunction "1_1") (pintype "passive"))
    )
    (net (code "86") (name "Net-(Q7-C)") (class "Default")
      (node (ref "Q7") (pin "3") (pinfunction "C_3") (pintype "passive"))
      (node (ref "R1") (pin "2") (pinfunction "2_2") (pintype "passive"))
      (node (ref "R91") (pin "1") (pinfunction "1_1") (pintype "passive"))
      (node (ref "U12") (pin "3") (pinfunction "~{SHDN}_3") (pintype "input"))
    )
    (net (code "87") (name "Net-(Q8-B)") (class "Default")
      (node (ref "Q8") (pin "1") (pinfunction "B_1") (pintype "passive"))
      (node (ref "R103") (pin "2") (pinfunction "2_2") (pintype "passive"))
      (node (ref "R81") (pin "2") (pinfunction "2_2") (pintype "passive"))
    )
    (net (code "88") (name "Net-(Q9-C)") (class "Default")
      (node (ref "Q9") (pin "3") (pinfunction "C_3") (pintype "passive"))
      (node (ref "R93") (pin "2") (pinfunction "2_2") (pintype "passive"))
    )
    (net (code "89") (name "Net-(U9-Y0)") (class "Default")
      (node (ref "R68") (pin "2") (pinfunction "2_2") (pintype "passive"))
      (node (ref "U9") (pin "2") (pinfunction "Y0_2") (pintype "bidirectional"))
    )
    (net (code "90") (name "Net-(U9-Y1)") (class "Default")
      (node (ref "R70") (pin "2") (pinfunction "2_2") (pintype "passive"))
      (node (ref "U9") (pin "1") (pinfunction "Y1_1") (pintype "bidirectional"))
    )
    (net (code "91") (name "Net-(U9-Z0)") (class "Default")
      (node (ref "R72") (pin "2") (pinfunction "2_2") (pintype "passive"))
      (node (ref "U9") (pin "5") (pinfunction "Z0_5") (pintype "bidirectional"))
    )
    (net (code "92") (name "Net-(U9-Z1)") (class "Default")
      (node (ref "R73") (pin "2") (pinfunction "2_2") (pintype "passive"))
      (node (ref "U9") (pin "3") (pinfunction "Z1_3") (pintype "bidirectional"))
    )
    (net (code "93") (name "Net-(U10-Y0)") (class "Default")
      (node (ref "R82") (pin "2") (pinfunction "2_2") (pintype "passive"))
      (node (ref "U10") (pin "2") (pinfunction "Y0_2") (pintype "bidirectional"))
    )
    (net (code "94") (name "Net-(U10-Y1)") (class "Default")
      (node (ref "R83") (pin "2") (pinfunction "2_2") (pintype "passive"))
      (node (ref "U10") (pin "1") (pinfunction "Y1_1") (pintype "bidirectional"))
    )
    (net (code "95") (name "Net-(U10-Z0)") (class "Default")
      (node (ref "R84") (pin "2") (pinfunction "2_2") (pintype "passive"))
      (node (ref "U10") (pin "5") (pinfunction "Z0_5") (pintype "bidirectional"))
    )
    (net (code "96") (name "Net-(U10-Z1)") (class "Default")
      (node (ref "R85") (pin "2") (pinfunction "2_2") (pintype "passive"))
      (node (ref "U10") (pin "3") (pinfunction "Z1_3") (pintype "bidirectional"))
    )
    (net (code "97") (name "Net-(U11-USBDM)") (class "Default")
      (node (ref "R89") (pin "2") (pinfunction "2_2") (pintype "passive"))
      (node (ref "U11") (pin "5") (pinfunction "USBDM_5") (pintype "bidirectional"))
    )
    (net (code "98") (name "Net-(U11-USBDP)") (class "Default")
      (node (ref "R88") (pin "2") (pinfunction "2_2") (pintype "passive"))
      (node (ref "U11") (pin "4") (pinfunction "USBDP_4") (pintype "bidirectional"))
    )
    (net (code "99") (name "PVCC3.3") (class "Default")
      (node (ref "C41") (pin "2") (pinfunction "2_2") (pintype "passive"))
      (node (ref "C42") (pin "2") (pinfunction "2_2") (pintype "passive"))
      (node (ref "C43") (pin "2") (pinfunction "2_2") (pintype "passive"))
      (node (ref "C44") (pin "2") (pinfunction "2_2") (pintype "passive"))
      (node (ref "C45") (pin "2") (pinfunction "2_2") (pintype "passive"))
      (node (ref "C46") (pin "2") (pinfunction "2_2") (pintype "passive"))
      (node (ref "C55") (pin "2") (pinfunction "2_2") (pintype "passive"))
      (node (ref "P10") (pin "2") (pinfunction "2_2") (pintype "passive"))
      (node (ref "P13") (pin "1") (pinfunction "1_1") (pintype "passive"))
      (node (ref "R79") (pin "2") (pinfunction "2_2") (pintype "passive"))
      (node (ref "R92") (pin "1") (pinfunction "1_1") (pintype "passive"))
      (node (ref "U10") (pin "16") (pinfunction "VCC_16") (pintype "power_in"))
      (node (ref "U8") (pin "1") (pinfunction "VBAT_1") (pintype "power_in"))
      (node (ref "U8") (pin "24") (pinfunction "VDD_1_24") (pintype "power_in"))
      (node (ref "U8") (pin "36") (pinfunction "VDD_2_36") (pintype "power_in"))
      (node (ref "U8") (pin "48") (pinfunction "VDD_3_48") (pintype "power_in"))
      (node (ref "U8") (pin "9") (pinfunction "VDDA_9") (pintype "power_in"))
      (node (ref "U9") (pin "16") (pinfunction "VCC_16") (pintype "power_in"))
    )
    (net (code "100") (name "USBVCC3V3") (class "Default")
      (node (ref "C47") (pin "1") (pinfunction "1_1") (pintype "passive"))
      (node (ref "C48") (pin "2") (pinfunction "2_2") (pintype "passive"))
      (node (ref "C56") (pin "2") (pinfunction "2_2") (pintype "passive"))
      (node (ref "D11") (pin "2") (pinfunction "A_2") (pintype "passive"))
      (node (ref "D13") (pin "2") (pinfunction "A_2") (pintype "passive"))
      (node (ref "R92") (pin "2") (pinfunction "2_2") (pintype "passive"))
      (node (ref "R98") (pin "1") (pinfunction "1_1") (pintype "passive"))
      (node (ref "U11") (pin "6") (pinfunction "REGOUT/3.3DVDD_6") (pintype "power_in"))
    )
    (net (code "101") (name "VBSS") (class "Default")
      (node (ref "C49") (pin "1") (pinfunction "1_1") (pintype "passive"))
      (node (ref "C50") (pin "2") (pinfunction "2_2") (pintype "passive"))
      (node (ref "C53") (pin "2") (pinfunction "2_2") (pintype "passive"))
      (node (ref "D1") (pin "5") (pinfunction "VP_5") (pintype "passive"))
      (node (ref "D18") (pin "2") (pinfunction "A_2") (pintype "passive"))
      (node (ref "Q8") (pin "2") (pinfunction "E_2") (pintype "passive"))
      (node (ref "R102") (pin "2") (pinfunction "2_2") (pintype "passive"))
      (node (ref "R104") (pin "1") (pinfunction "1_1") (pintype "passive"))
      (node (ref "R91") (pin "2") (pinfunction "2_2") (pintype "passive"))
      (node (ref "U11") (pin "7") (pinfunction "REGIN_7") (pintype "power_in"))
      (node (ref "U11") (pin "8") (pinfunction "VBUS_8") (pintype "power_in"))
      (node (ref "U12") (pin "1") (pinfunction "VIN_1") (pintype "power_in"))
      (node (ref "X3") (pin "1") (pinfunction "V+_1") (pintype "passive"))
    )
    (net (code "102") (name "VCCPROG") (class "Default")
      (node (ref "C51") (pin "1") (pinfunction "1_1") (pintype "passive"))
      (node (ref "P11") (pin "1") (pinfunction "1_1") (pintype "passive"))
      (node (ref "P9") (pin "2") (pinfunction "2_2") (pintype "passive"))
      (node (ref "R55") (pin "2") (pinfunction "2_2") (pintype "passive"))
      (node (ref "R68") (pin "1") (pinfunction "1_1") (pintype "passive"))
      (node (ref "R72") (pin "1") (pinfunction "1_1") (pintype "passive"))
      (node (ref "R82") (pin "1") (pinfunction "1_1") (pintype "passive"))
      (node (ref "R84") (pin "1") (pinfunction "1_1") (pintype "passive"))
      (node (ref "U12") (pin "5") (pinfunction "VOUT_5") (pintype "power_in"))
    )
    (net (code "103") (name "unconnected-(P11-Pad8)") (class "Default")
      (node (ref "P11") (pin "8") (pinfunction "8_8") (pintype "passive+no_connect"))
    )
    (net (code "104") (name "unconnected-(P18-Pad8)") (class "Default")
      (node (ref "P18") (pin "8") (pinfunction "8_8") (pintype "passive+no_connect"))
    )
    (net (code "105") (name "unconnected-(P25-Pad8)") (class "Default")
      (node (ref "P25") (pin "8") (pinfunction "8_8") (pintype "passive+no_connect"))
    )
    (net (code "106") (name "unconnected-(U8A-PA0-WKUP-Pad10)") (class "Default")
      (node (ref "U8") (pin "10") (pinfunction "PA0-WKUP_10") (pintype "bidirectional"))
    )
    (net (code "107") (name "unconnected-(U8A-PA12-Pad33)") (class "Default")
      (node (ref "U8") (pin "33") (pinfunction "PA12_33") (pintype "bidirectional"))
    )
    (net (code "108") (name "unconnected-(U9-X-Pad14)") (class "Default")
      (node (ref "U9") (pin "14") (pinfunction "X_14") (pintype "bidirectional+no_connect"))
    )
    (net (code "109") (name "unconnected-(U9-X0-Pad12)") (class "Default")
      (node (ref "U9") (pin "12") (pinfunction "X0_12") (pintype "bidirectional+no_connect"))
    )
    (net (code "110") (name "unconnected-(U9-X1-Pad13)") (class "Default")
      (node (ref "U9") (pin "13") (pinfunction "X1_13") (pintype "bidirectional+no_connect"))
    )
    (net (code "111") (name "unconnected-(U10-X-Pad14)") (class "Default")
      (node (ref "U10") (pin "14") (pinfunction "X_14") (pintype "bidirectional+no_connect"))
    )
    (net (code "112") (name "unconnected-(U10-X0-Pad12)") (class "Default")
      (node (ref "U10") (pin "12") (pinfunction "X0_12") (pintype "bidirectional+no_connect"))
    )
    (net (code "113") (name "unconnected-(U10-X1-Pad13)") (class "Default")
      (node (ref "U10") (pin "13") (pinfunction "X1_13") (pintype "bidirectional+no_connect"))
    )
    (net (code "114") (name "unconnected-(U11-NC-Pad10)") (class "Default")
      (node (ref "U11") (pin "10") (pinfunction "NC_10") (pintype "passive+no_connect"))
    )
    (net (code "115") (name "unconnected-(U11-NC-Pad13)") (class "Default")
      (node (ref "U11") (pin "13") (pinfunction "NC_13") (pintype "passive+no_connect"))
    )
    (net (code "116") (name "unconnected-(U11-NC-Pad14)") (class "Default")
      (node (ref "U11") (pin "14") (pinfunction "NC_14") (pintype "passive+no_connect"))
    )
    (net (code "117") (name "unconnected-(U11-NC-Pad15)") (class "Default")
      (node (ref "U11") (pin "15") (pinfunction "NC_15") (pintype "passive+no_connect"))
    )
    (net (code "118") (name "unconnected-(U11-NC-Pad16)") (class "Default")
      (node (ref "U11") (pin "16") (pinfunction "NC_16") (pintype "passive+no_connect"))
    )
    (net (code "119") (name "unconnected-(U11-NC-Pad17)") (class "Default")
      (node (ref "U11") (pin "17") (pinfunction "NC_17") (pintype "passive+no_connect"))
    )
    (net (code "120") (name "unconnected-(U11-NC-Pad18)") (class "Default")
      (node (ref "U11") (pin "18") (pinfunction "NC_18") (pintype "passive+no_connect"))
    )
    (net (code "121") (name "unconnected-(U11-NC-Pad19)") (class "Default")
      (node (ref "U11") (pin "19") (pinfunction "NC_19") (pintype "passive+no_connect"))
    )
    (net (code "122") (name "unconnected-(U11-NC-Pad20)") (class "Default")
      (node (ref "U11") (pin "20") (pinfunction "NC_20") (pintype "passive+no_connect"))
    )
    (net (code "123") (name "unconnected-(U11-NC-Pad21)") (class "Default")
      (node (ref "U11") (pin "21") (pinfunction "NC_21") (pintype "passive+no_connect"))
    )
    (net (code "124") (name "unconnected-(U11-NC-Pad22)") (class "Default")
      (node (ref "U11") (pin "22") (pinfunction "NC_22") (pintype "passive+no_connect"))
    )
    (net (code "125") (name "unconnected-(U11-SUSPEND-Pad12)") (class "Default")
      (node (ref "U11") (pin "12") (pinfunction "SUSPEND_12") (pintype "output+no_connect"))
    )
    (net (code "126") (name "unconnected-(U12-PWRGD-Pad4)") (class "Default")
      (node (ref "U12") (pin "4") (pinfunction "PWRGD_4") (pintype "power_in+no_connect"))
    )
  )
)
